# C64_KernalSw_8k.net
KiCad netlist of a schematic drawn in EAGLE
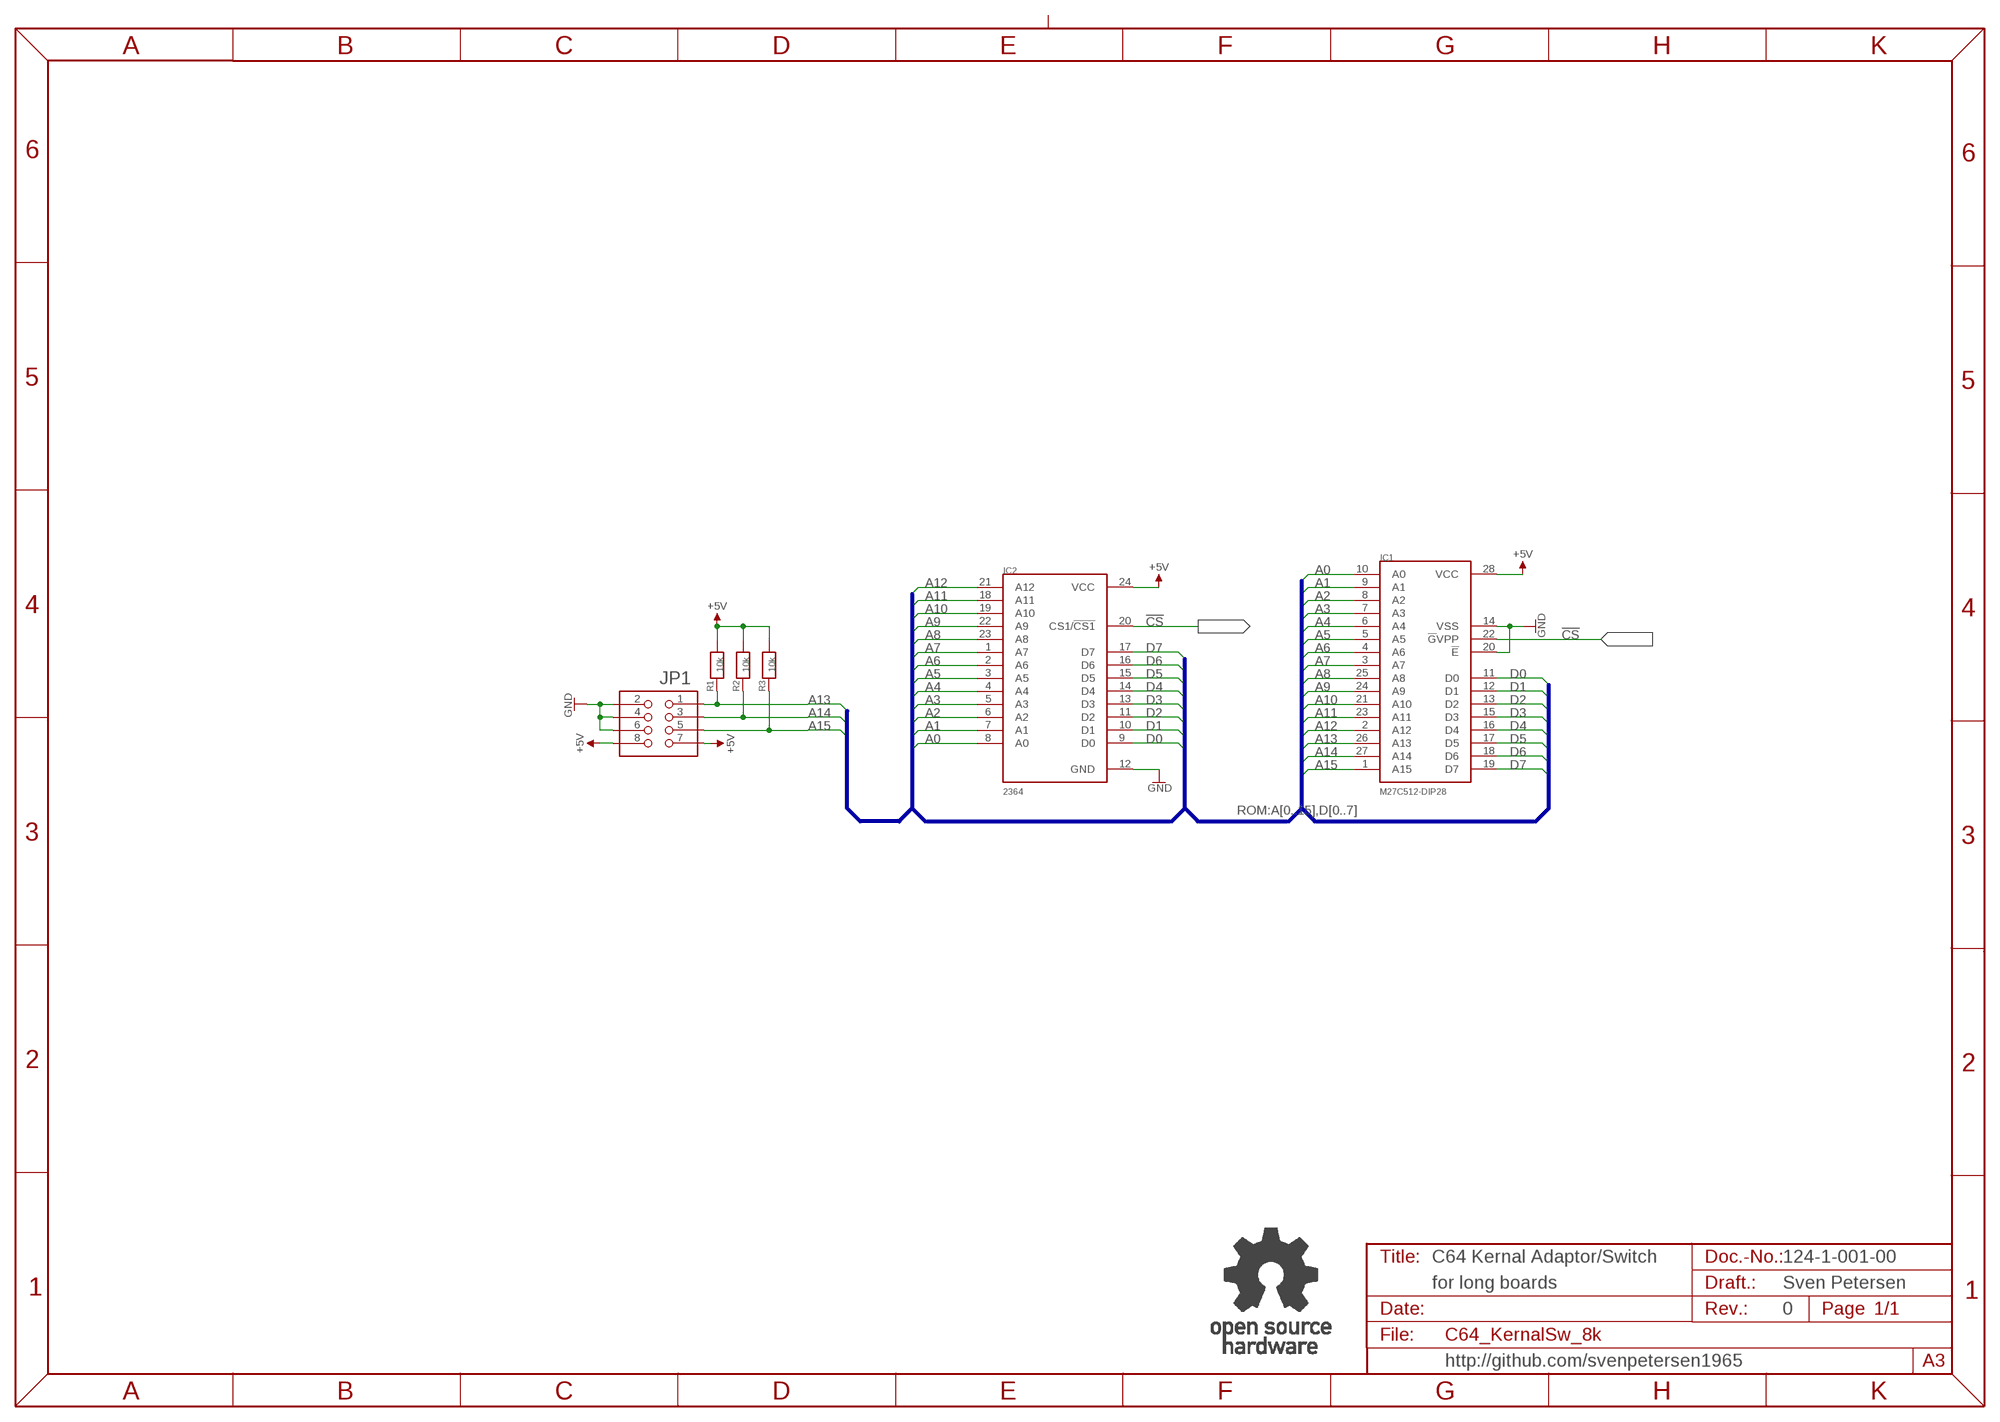
[diagram p0: schematic, sheet 1]

(export (version "E")
  (design (tool "Eeschema 10.0.6"))
  (components
    (comp (ref "IC1")
      (value "M27C512-DIP28")
      (footprint "eagle-import:DIL28-6")
      (libsource (lib "eagle-import") (part "M27C512-DIP28"))
    )
    (comp (ref "IC2")
      (value "2364")
      (footprint "eagle-import:DIL24_SOCKET")
      (libsource (lib "eagle-import") (part "2364"))
    )
    (comp (ref "JP1")
      (value "PINHD-2X490°/MPE_088")
      (footprint "eagle-import:2X04_90_SERIES_088")
      (libsource (lib "eagle-import") (part "PINHD-2X490°/MPE_088"))
    )
    (comp (ref "R1")
      (value "10k")
      (footprint "eagle-import:0805")
      (libsource (lib "eagle-import") (part "R-0805"))
    )
    (comp (ref "R2")
      (value "10k")
      (footprint "eagle-import:0805")
      (libsource (lib "eagle-import") (part "R-0805"))
    )
    (comp (ref "R3")
      (value "10k")
      (footprint "eagle-import:0805")
      (libsource (lib "eagle-import") (part "R-0805"))
    )
    (comp (ref "U$11")
      (value "OPEN_SOURCE_HW")
      (footprint "eagle-import:OPENHW")
      (libsource (lib "eagle-import") (part "OPEN_SOURCE_HW"))
    )
  )
  (nets
    (net (code "1") (name "+5V") (class "Default")
      (node (ref "IC1") (pin "28") (pinfunction "VCC_28") (pintype "power_in"))
      (node (ref "IC2") (pin "24") (pinfunction "VCC_24") (pintype "power_in"))
      (node (ref "JP1") (pin "7") (pinfunction "7_7") (pintype "passive"))
      (node (ref "JP1") (pin "8") (pinfunction "8_8") (pintype "passive"))
      (node (ref "R1") (pin "2") (pinfunction "2_2") (pintype "passive"))
      (node (ref "R2") (pin "2") (pinfunction "2_2") (pintype "passive"))
      (node (ref "R3") (pin "2") (pinfunction "2_2") (pintype "passive"))
    )
    (net (code "2") (name "/A0") (class "Default")
      (node (ref "IC1") (pin "10") (pinfunction "A0_10") (pintype "input"))
      (node (ref "IC2") (pin "8") (pinfunction "A0_8") (pintype "input"))
    )
    (net (code "3") (name "/A1") (class "Default")
      (node (ref "IC1") (pin "9") (pinfunction "A1_9") (pintype "input"))
      (node (ref "IC2") (pin "7") (pinfunction "A1_7") (pintype "input"))
    )
    (net (code "4") (name "/A2") (class "Default")
      (node (ref "IC1") (pin "8") (pinfunction "A2_8") (pintype "input"))
      (node (ref "IC2") (pin "6") (pinfunction "A2_6") (pintype "input"))
    )
    (net (code "5") (name "/A3") (class "Default")
      (node (ref "IC1") (pin "7") (pinfunction "A3_7") (pintype "input"))
      (node (ref "IC2") (pin "5") (pinfunction "A3_5") (pintype "input"))
    )
    (net (code "6") (name "/A4") (class "Default")
      (node (ref "IC1") (pin "6") (pinfunction "A4_6") (pintype "input"))
      (node (ref "IC2") (pin "4") (pinfunction "A4_4") (pintype "input"))
    )
    (net (code "7") (name "/A5") (class "Default")
      (node (ref "IC1") (pin "5") (pinfunction "A5_5") (pintype "input"))
      (node (ref "IC2") (pin "3") (pinfunction "A5_3") (pintype "input"))
    )
    (net (code "8") (name "/A6") (class "Default")
      (node (ref "IC1") (pin "4") (pinfunction "A6_4") (pintype "input"))
      (node (ref "IC2") (pin "2") (pinfunction "A6_2") (pintype "input"))
    )
    (net (code "9") (name "/A7") (class "Default")
      (node (ref "IC1") (pin "3") (pinfunction "A7_3") (pintype "input"))
      (node (ref "IC2") (pin "1") (pinfunction "A7_1") (pintype "input"))
    )
    (net (code "10") (name "/A8") (class "Default")
      (node (ref "IC1") (pin "25") (pinfunction "A8_25") (pintype "input"))
      (node (ref "IC2") (pin "23") (pinfunction "A8_23") (pintype "input"))
    )
    (net (code "11") (name "/A9") (class "Default")
      (node (ref "IC1") (pin "24") (pinfunction "A9_24") (pintype "input"))
      (node (ref "IC2") (pin "22") (pinfunction "A9_22") (pintype "input"))
    )
    (net (code "12") (name "/A10") (class "Default")
      (node (ref "IC1") (pin "21") (pinfunction "A10_21") (pintype "input"))
      (node (ref "IC2") (pin "19") (pinfunction "A10_19") (pintype "input"))
    )
    (net (code "13") (name "/A11") (class "Default")
      (node (ref "IC1") (pin "23") (pinfunction "A11_23") (pintype "input"))
      (node (ref "IC2") (pin "18") (pinfunction "A11_18") (pintype "input"))
    )
    (net (code "14") (name "/A12") (class "Default")
      (node (ref "IC1") (pin "2") (pinfunction "A12_2") (pintype "input"))
      (node (ref "IC2") (pin "21") (pinfunction "A12_21") (pintype "input"))
    )
    (net (code "15") (name "/A13") (class "Default")
      (node (ref "IC1") (pin "26") (pinfunction "A13_26") (pintype "input"))
      (node (ref "JP1") (pin "1") (pinfunction "1_1") (pintype "passive"))
      (node (ref "R1") (pin "1") (pinfunction "1_1") (pintype "passive"))
    )
    (net (code "16") (name "/A14") (class "Default")
      (node (ref "IC1") (pin "27") (pinfunction "A14_27") (pintype "input"))
      (node (ref "JP1") (pin "3") (pinfunction "3_3") (pintype "passive"))
      (node (ref "R2") (pin "1") (pinfunction "1_1") (pintype "passive"))
    )
    (net (code "17") (name "/A15") (class "Default")
      (node (ref "IC1") (pin "1") (pinfunction "A15_1") (pintype "input"))
      (node (ref "JP1") (pin "5") (pinfunction "5_5") (pintype "passive"))
      (node (ref "R3") (pin "1") (pinfunction "1_1") (pintype "passive"))
    )
    (net (code "18") (name "/D0") (class "Default")
      (node (ref "IC1") (pin "11") (pinfunction "D0_11") (pintype "bidirectional"))
      (node (ref "IC2") (pin "9") (pinfunction "D0_9") (pintype "tri_state"))
    )
    (net (code "19") (name "/D1") (class "Default")
      (node (ref "IC1") (pin "12") (pinfunction "D1_12") (pintype "bidirectional"))
      (node (ref "IC2") (pin "10") (pinfunction "D1_10") (pintype "tri_state"))
    )
    (net (code "20") (name "/D2") (class "Default")
      (node (ref "IC1") (pin "13") (pinfunction "D2_13") (pintype "bidirectional"))
      (node (ref "IC2") (pin "11") (pinfunction "D2_11") (pintype "tri_state"))
    )
    (net (code "21") (name "/D3") (class "Default")
      (node (ref "IC1") (pin "15") (pinfunction "D3_15") (pintype "bidirectional"))
      (node (ref "IC2") (pin "13") (pinfunction "D3_13") (pintype "tri_state"))
    )
    (net (code "22") (name "/D4") (class "Default")
      (node (ref "IC1") (pin "16") (pinfunction "D4_16") (pintype "bidirectional"))
      (node (ref "IC2") (pin "14") (pinfunction "D4_14") (pintype "tri_state"))
    )
    (net (code "23") (name "/D5") (class "Default")
      (node (ref "IC1") (pin "17") (pinfunction "D5_17") (pintype "bidirectional"))
      (node (ref "IC2") (pin "15") (pinfunction "D5_15") (pintype "tri_state"))
    )
    (net (code "24") (name "/D6") (class "Default")
      (node (ref "IC1") (pin "18") (pinfunction "D6_18") (pintype "bidirectional"))
      (node (ref "IC2") (pin "16") (pinfunction "D6_16") (pintype "tri_state"))
    )
    (net (code "25") (name "/D7") (class "Default")
      (node (ref "IC1") (pin "19") (pinfunction "D7_19") (pintype "bidirectional"))
      (node (ref "IC2") (pin "17") (pinfunction "D7_17") (pintype "tri_state"))
    )
    (net (code "27") (name "/~{CS}") (class "Default")
      (node (ref "IC1") (pin "22") (pinfunction "~{G}VPP_22") (pintype "input"))
      (node (ref "IC2") (pin "20") (pinfunction "CS1/~{CS1}_20") (pintype "input"))
    )
    (net (code "28") (name "GND") (class "Default")
      (node (ref "IC1") (pin "14") (pinfunction "VSS_14") (pintype "power_in"))
      (node (ref "IC1") (pin "20") (pinfunction "~{E}_20") (pintype "input"))
      (node (ref "IC2") (pin "12") (pinfunction "GND_12") (pintype "power_in"))
      (node (ref "JP1") (pin "2") (pinfunction "2_2") (pintype "passive"))
      (node (ref "JP1") (pin "4") (pinfunction "4_4") (pintype "passive"))
      (node (ref "JP1") (pin "6") (pinfunction "6_6") (pintype "passive"))
    )
  )
)
